# signal_processing_module.net
KiCad netlist of a schematic drawn in EAGLE
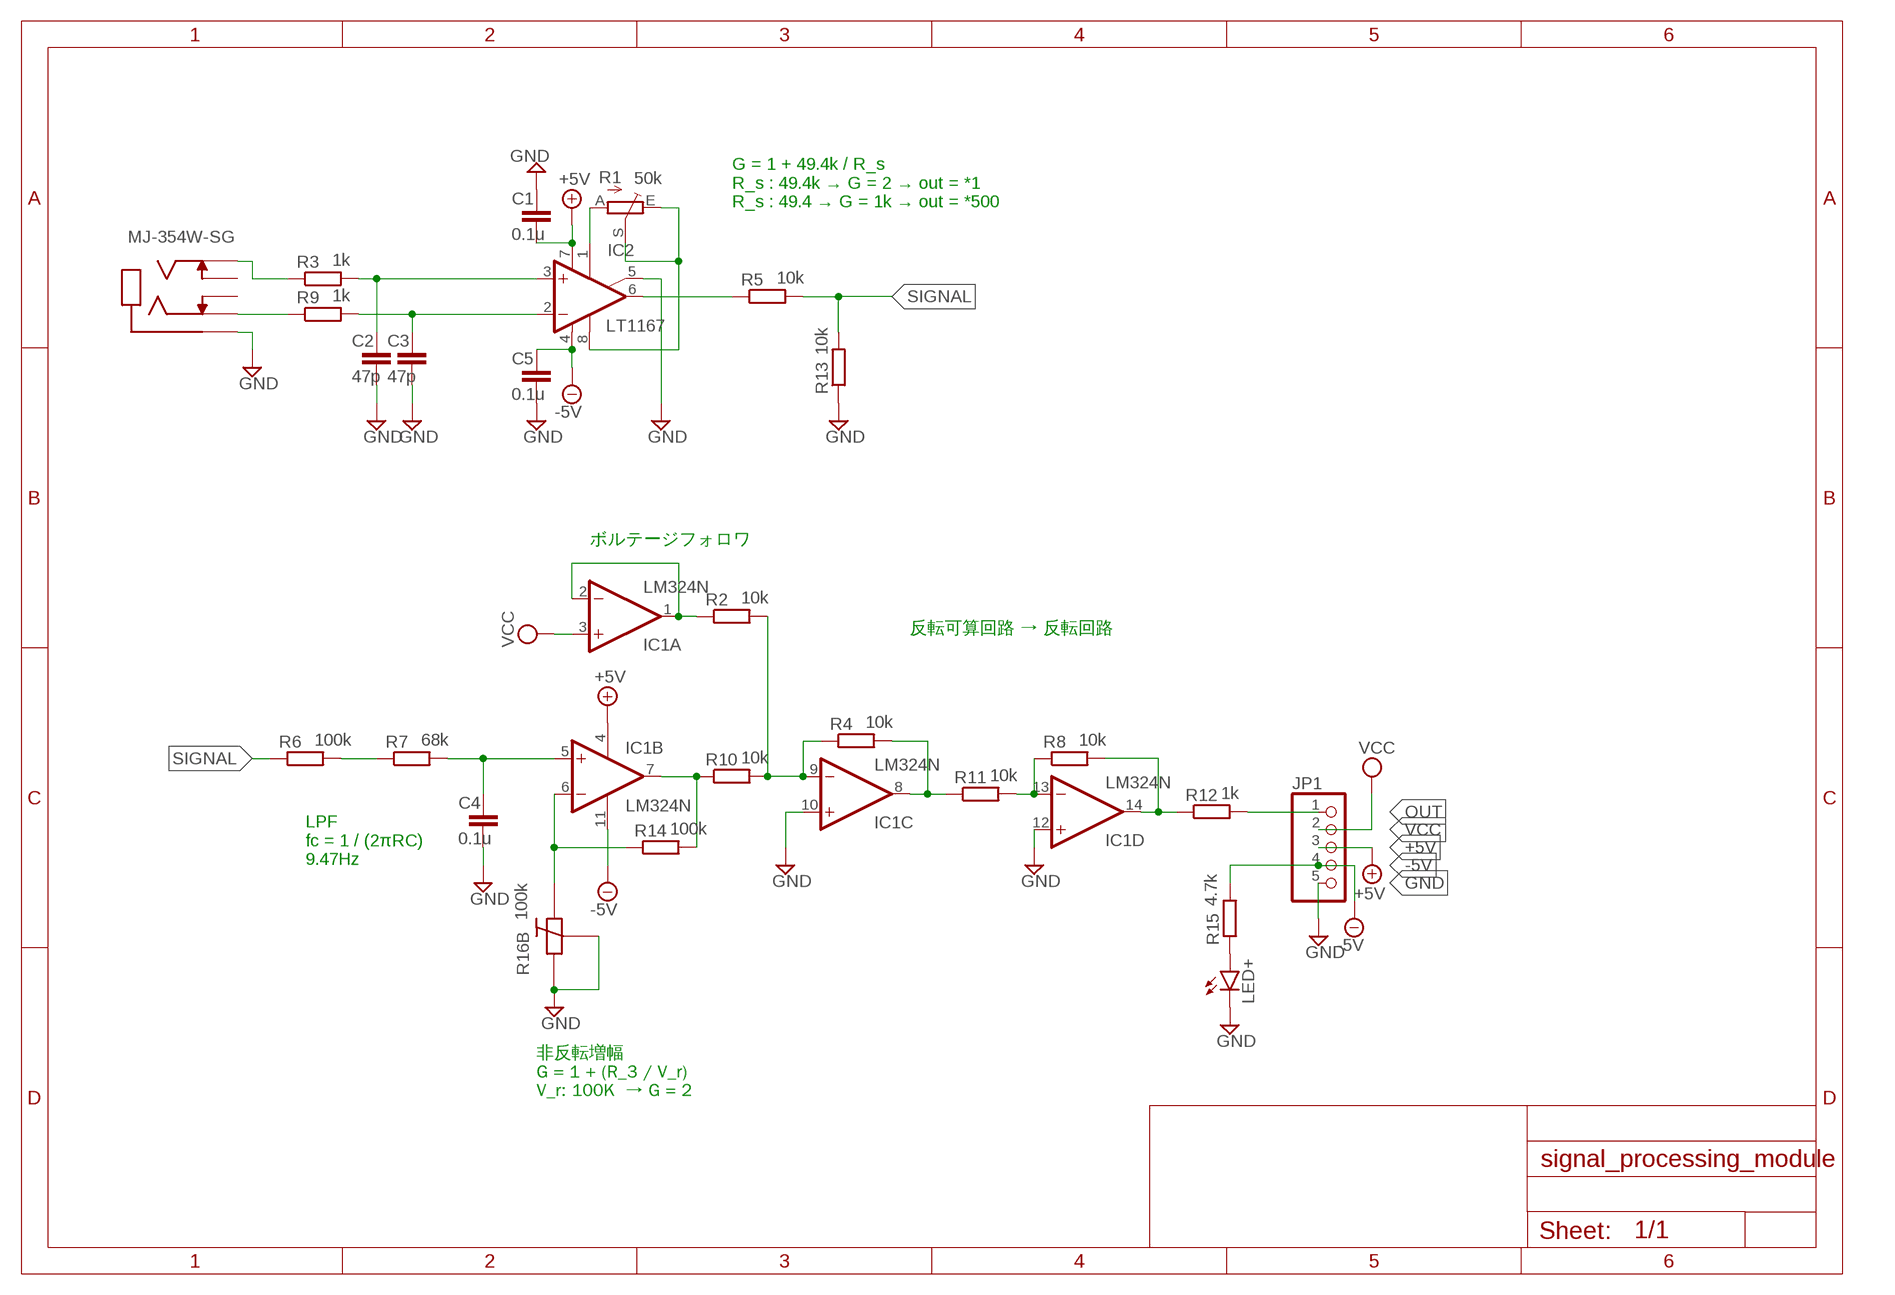
[diagram p0: schematic, sheet 1]

(export (version "E")
  (design (tool "Eeschema 10.0.6"))
  (components
    (comp (ref "C1")
      (value "0.1u")
      (footprint "eagle-import:C025-024X044")
      (libsource (lib "eagle-import") (part "C-EU025-024X044"))
    )
    (comp (ref "C2")
      (value "47p")
      (footprint "eagle-import:C025-024X044")
      (libsource (lib "eagle-import") (part "C-EU025-024X044"))
    )
    (comp (ref "C3")
      (value "47p")
      (footprint "eagle-import:C025-024X044")
      (libsource (lib "eagle-import") (part "C-EU025-024X044"))
    )
    (comp (ref "C4")
      (value "0.1u")
      (footprint "eagle-import:C025-024X044")
      (libsource (lib "eagle-import") (part "C-EU025-024X044"))
    )
    (comp (ref "C5")
      (value "0.1u")
      (footprint "eagle-import:C025-024X044")
      (libsource (lib "eagle-import") (part "C-EU025-024X044"))
    )
    (comp (ref "IC1")
      (value "LM324N")
      (footprint "eagle-import:DIL14")
      (libsource (lib "eagle-import") (part "LM324N"))
    )
    (comp (ref "IC2")
      (value "TL061P")
      (footprint "eagle-import:DIL08")
      (libsource (lib "eagle-import") (part "TL061P"))
    )
    (comp (ref "JP1")
      (value "PINHD-1X5")
      (footprint "eagle-import:1X05")
      (libsource (lib "eagle-import") (part "PINHD-1X5"))
    )
    (comp (ref "LED+")
      (value "LED3MM")
      (footprint "eagle-import:LED3MM")
      (libsource (lib "eagle-import") (part "LED3MM"))
    )
    (comp (ref "R1")
      (value "50k")
      (footprint "eagle-import:RS3")
      (libsource (lib "eagle-import") (part "TRIM_EU-RS3"))
    )
    (comp (ref "R2")
      (value "10k")
      (footprint "eagle-import:0204_7")
      (libsource (lib "eagle-import") (part "R-EU_0204/7"))
    )
    (comp (ref "R3")
      (value "1k")
      (footprint "eagle-import:0204_7")
      (libsource (lib "eagle-import") (part "R-EU_0204/7"))
    )
    (comp (ref "R4")
      (value "10k")
      (footprint "eagle-import:0204_7")
      (libsource (lib "eagle-import") (part "R-EU_0204/7"))
    )
    (comp (ref "R5")
      (value "10k")
      (footprint "eagle-import:0204_7")
      (libsource (lib "eagle-import") (part "R-EU_0204/7"))
    )
    (comp (ref "R6")
      (value "100k")
      (footprint "eagle-import:0204_7")
      (libsource (lib "eagle-import") (part "R-EU_0204/7"))
    )
    (comp (ref "R7")
      (value "68k")
      (footprint "eagle-import:0204_7")
      (libsource (lib "eagle-import") (part "R-EU_0204/7"))
    )
    (comp (ref "R8")
      (value "10k")
      (footprint "eagle-import:0204_7")
      (libsource (lib "eagle-import") (part "R-EU_0204/7"))
    )
    (comp (ref "R9")
      (value "1k")
      (footprint "eagle-import:0204_7")
      (libsource (lib "eagle-import") (part "R-EU_0204/7"))
    )
    (comp (ref "R10")
      (value "10k")
      (footprint "eagle-import:0204_7")
      (libsource (lib "eagle-import") (part "R-EU_0204/7"))
    )
    (comp (ref "R11")
      (value "10k")
      (footprint "eagle-import:0204_7")
      (libsource (lib "eagle-import") (part "R-EU_0204/7"))
    )
    (comp (ref "R12")
      (value "1k")
      (footprint "eagle-import:0204_7")
      (libsource (lib "eagle-import") (part "R-EU_0204/7"))
    )
    (comp (ref "R13")
      (value "10k")
      (footprint "eagle-import:0204_7")
      (libsource (lib "eagle-import") (part "R-EU_0204/7"))
    )
    (comp (ref "R14")
      (value "100k")
      (footprint "eagle-import:0204_7")
      (libsource (lib "eagle-import") (part "R-EU_0204/7"))
    )
    (comp (ref "R15")
      (value "4.7k")
      (footprint "eagle-import:0204_7")
      (libsource (lib "eagle-import") (part "R-EU_0204/7"))
    )
    (comp (ref "R16")
      (value "100k")
      (footprint "eagle-import:2CH_VR")
      (libsource (lib "eagle-import") (part "VR_2CH"))
    )
    (comp (ref "U$1")
      (value "MJ-354W-SG-NEW")
      (footprint "eagle-import:MJ-354W-SG")
      (libsource (lib "eagle-import") (part "MJ-354W-SG-NEW"))
    )
  )
  (nets
    (net (code "1") (name "+5V") (class "Default")
      (node (ref "C1") (pin "2") (pinfunction "2_2") (pintype "passive"))
      (node (ref "IC1") (pin "4") (pinfunction "V+_4") (pintype "power_in"))
      (node (ref "IC2") (pin "7") (pinfunction "V+_7") (pintype "power_in"))
      (node (ref "JP1") (pin "3") (pinfunction "3_3") (pintype "passive"))
    )
    (net (code "2") (name "-5V") (class "Default")
      (node (ref "C5") (pin "1") (pinfunction "1_1") (pintype "passive"))
      (node (ref "IC1") (pin "11") (pinfunction "V-_11") (pintype "power_in"))
      (node (ref "IC2") (pin "4") (pinfunction "V-_4") (pintype "power_in"))
      (node (ref "JP1") (pin "4") (pinfunction "4_4") (pintype "passive"))
      (node (ref "R15") (pin "2") (pinfunction "2_2") (pintype "passive"))
    )
    (net (code "3") (name "GND") (class "Default")
      (node (ref "C1") (pin "1") (pinfunction "1_1") (pintype "passive"))
      (node (ref "C2") (pin "2") (pinfunction "2_2") (pintype "passive"))
      (node (ref "C3") (pin "2") (pinfunction "2_2") (pintype "passive"))
      (node (ref "C4") (pin "2") (pinfunction "2_2") (pintype "passive"))
      (node (ref "C5") (pin "2") (pinfunction "2_2") (pintype "passive"))
      (node (ref "IC1") (pin "10") (pinfunction "+IN_10") (pintype "input"))
      (node (ref "IC1") (pin "12") (pinfunction "+IN_12") (pintype "input"))
      (node (ref "IC2") (pin "5") (pinfunction "ON2_5") (pintype "passive"))
      (node (ref "JP1") (pin "5") (pinfunction "5_5") (pintype "passive"))
      (node (ref "LED+") (pin "K") (pinfunction "C_K") (pintype "passive"))
      (node (ref "R13") (pin "1") (pinfunction "1_1") (pintype "passive"))
      (node (ref "R16") (pin "P$4") (pinfunction "P$1_P$4") (pintype "bidirectional"))
      (node (ref "R16") (pin "P$5") (pinfunction "P$2_P$5") (pintype "bidirectional"))
      (node (ref "U$1") (pin "P$1") (pinfunction "P$1_P$1") (pintype "bidirectional"))
    )
    (net (code "4") (name "Net-(IC1A--IN)") (class "Default")
      (node (ref "IC1") (pin "1") (pinfunction "OUT_1") (pintype "output"))
      (node (ref "IC1") (pin "2") (pinfunction "-IN_2") (pintype "input"))
      (node (ref "R2") (pin "1") (pinfunction "1_1") (pintype "passive"))
    )
    (net (code "5") (name "Net-(IC1B-+IN)") (class "Default")
      (node (ref "C4") (pin "1") (pinfunction "1_1") (pintype "passive"))
      (node (ref "IC1") (pin "5") (pinfunction "+IN_5") (pintype "input"))
      (node (ref "R7") (pin "2") (pinfunction "2_2") (pintype "passive"))
    )
    (net (code "6") (name "Net-(IC1B--IN)") (class "Default")
      (node (ref "IC1") (pin "6") (pinfunction "-IN_6") (pintype "input"))
      (node (ref "R14") (pin "1") (pinfunction "1_1") (pintype "passive"))
      (node (ref "R16") (pin "P$6") (pinfunction "P$3_P$6") (pintype "bidirectional"))
    )
    (net (code "7") (name "Net-(IC1B-OUT)") (class "Default")
      (node (ref "IC1") (pin "7") (pinfunction "OUT_7") (pintype "output"))
      (node (ref "R10") (pin "1") (pinfunction "1_1") (pintype "passive"))
      (node (ref "R14") (pin "2") (pinfunction "2_2") (pintype "passive"))
    )
    (net (code "8") (name "Net-(IC1C--IN)") (class "Default")
      (node (ref "IC1") (pin "9") (pinfunction "-IN_9") (pintype "input"))
      (node (ref "R10") (pin "2") (pinfunction "2_2") (pintype "passive"))
      (node (ref "R2") (pin "2") (pinfunction "2_2") (pintype "passive"))
      (node (ref "R4") (pin "1") (pinfunction "1_1") (pintype "passive"))
    )
    (net (code "9") (name "Net-(IC1C-OUT)") (class "Default")
      (node (ref "IC1") (pin "8") (pinfunction "OUT_8") (pintype "output"))
      (node (ref "R11") (pin "1") (pinfunction "1_1") (pintype "passive"))
      (node (ref "R4") (pin "2") (pinfunction "2_2") (pintype "passive"))
    )
    (net (code "10") (name "Net-(IC1D--IN)") (class "Default")
      (node (ref "IC1") (pin "13") (pinfunction "-IN_13") (pintype "input"))
      (node (ref "R11") (pin "2") (pinfunction "2_2") (pintype "passive"))
      (node (ref "R8") (pin "1") (pinfunction "1_1") (pintype "passive"))
    )
    (net (code "11") (name "Net-(IC1D-OUT)") (class "Default")
      (node (ref "IC1") (pin "14") (pinfunction "OUT_14") (pintype "output"))
      (node (ref "R12") (pin "1") (pinfunction "1_1") (pintype "passive"))
      (node (ref "R8") (pin "2") (pinfunction "2_2") (pintype "passive"))
    )
    (net (code "12") (name "Net-(IC2-+IN)") (class "Default")
      (node (ref "C2") (pin "1") (pinfunction "1_1") (pintype "passive"))
      (node (ref "IC2") (pin "3") (pinfunction "+IN_3") (pintype "input"))
      (node (ref "R3") (pin "2") (pinfunction "2_2") (pintype "passive"))
    )
    (net (code "13") (name "Net-(IC2--IN)") (class "Default")
      (node (ref "C3") (pin "1") (pinfunction "1_1") (pintype "passive"))
      (node (ref "IC2") (pin "2") (pinfunction "-IN_2") (pintype "input"))
      (node (ref "R9") (pin "2") (pinfunction "2_2") (pintype "passive"))
    )
    (net (code "14") (name "Net-(IC2-ON1)") (class "Default")
      (node (ref "IC2") (pin "1") (pinfunction "ON1_1") (pintype "passive"))
      (node (ref "R1") (pin "A") (pinfunction "A_A") (pintype "passive"))
    )
    (net (code "15") (name "Net-(IC2-OPT)") (class "Default")
      (node (ref "IC2") (pin "8") (pinfunction "OPT_8") (pintype "passive"))
      (node (ref "R1") (pin "E") (pinfunction "E_E") (pintype "passive"))
      (node (ref "R1") (pin "S") (pinfunction "S_S") (pintype "passive"))
    )
    (net (code "16") (name "Net-(IC2-OUT)") (class "Default")
      (node (ref "IC2") (pin "6") (pinfunction "OUT_6") (pintype "output"))
      (node (ref "R5") (pin "1") (pinfunction "1_1") (pintype "passive"))
    )
    (net (code "17") (name "Net-(LED+-PadA)") (class "Default")
      (node (ref "LED+") (pin "A") (pinfunction "A_A") (pintype "passive"))
      (node (ref "R15") (pin "1") (pinfunction "1_1") (pintype "passive"))
    )
    (net (code "18") (name "Net-(R3-Pad1)") (class "Default")
      (node (ref "R3") (pin "1") (pinfunction "1_1") (pintype "passive"))
      (node (ref "U$1") (pin "P$4") (pinfunction "P$4_P$4") (pintype "bidirectional"))
    )
    (net (code "19") (name "Net-(R6-Pad2)") (class "Default")
      (node (ref "R6") (pin "2") (pinfunction "2_2") (pintype "passive"))
      (node (ref "R7") (pin "1") (pinfunction "1_1") (pintype "passive"))
    )
    (net (code "20") (name "Net-(R9-Pad1)") (class "Default")
      (node (ref "R9") (pin "1") (pinfunction "1_1") (pintype "passive"))
      (node (ref "U$1") (pin "P$2") (pinfunction "P$2_P$2") (pintype "bidirectional"))
    )
    (net (code "21") (name "OUT") (class "Default")
      (node (ref "JP1") (pin "1") (pinfunction "1_1") (pintype "passive"))
      (node (ref "R12") (pin "2") (pinfunction "2_2") (pintype "passive"))
    )
    (net (code "22") (name "SIGNAL") (class "Default")
      (node (ref "R13") (pin "2") (pinfunction "2_2") (pintype "passive"))
      (node (ref "R5") (pin "2") (pinfunction "2_2") (pintype "passive"))
      (node (ref "R6") (pin "1") (pinfunction "1_1") (pintype "passive"))
    )
    (net (code "23") (name "VCC") (class "Default")
      (node (ref "IC1") (pin "3") (pinfunction "+IN_3") (pintype "input"))
      (node (ref "JP1") (pin "2") (pinfunction "2_2") (pintype "passive"))
    )
    (net (code "24") (name "unconnected-(U$1-PadP$3)") (class "Default")
      (node (ref "U$1") (pin "P$3") (pinfunction "P$3_P$3") (pintype "bidirectional"))
    )
    (net (code "25") (name "unconnected-(U$1-PadP$5)") (class "Default")
      (node (ref "U$1") (pin "P$5") (pinfunction "P$5_P$5") (pintype "bidirectional"))
    )
  )
)
